# design.net
KiCad netlist of a schematic drawn in Altium Designer
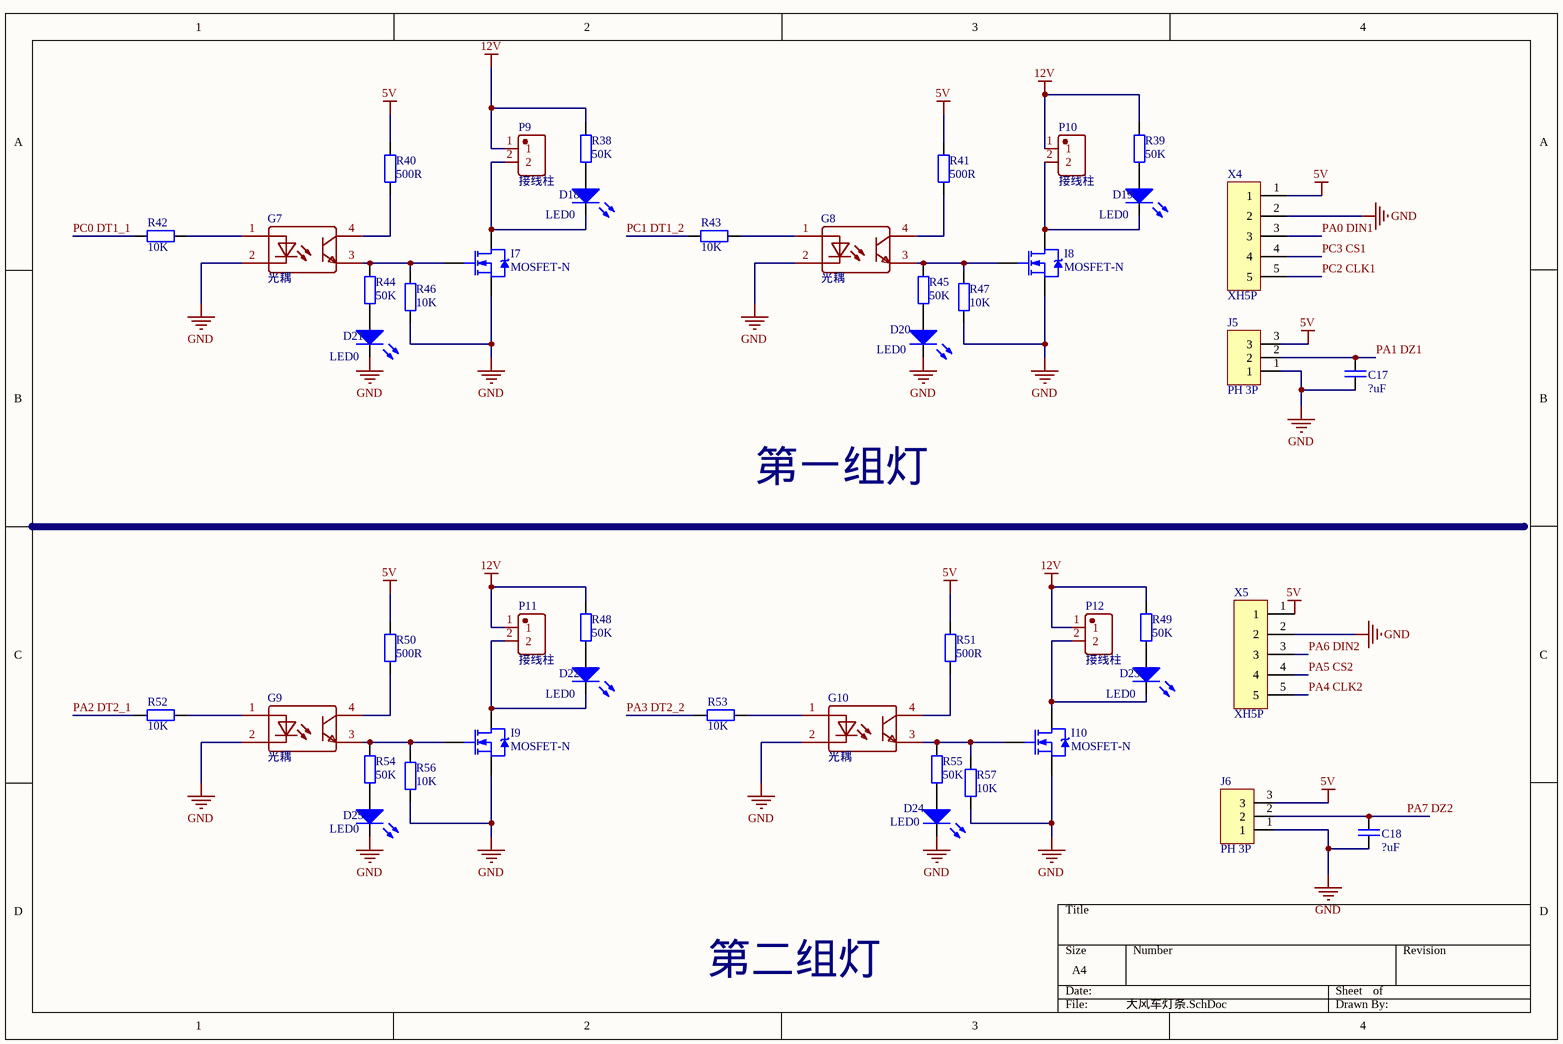
[diagram p0: 大风车灯条.SchDoc]

(export (version "E")
  (design (tool "Eeschema 10.0.6"))
  (components
    (comp (ref "C17")
      (value "?uF")
      (footprint "0603_C")
      (fields (field (name "PUBLISHER") "Altium Limited"))
      (libsource (lib "电容-电阻-电感") (part "Cap"))
    )
    (comp (ref "C18")
      (value "?uF")
      (footprint "0603_C")
      (fields (field (name "PUBLISHER") "Altium Limited"))
      (libsource (lib "电容-电阻-电感") (part "Cap"))
    )
    (comp (ref "D18")
      (value "LED0")
      (footprint "LED-0603")
      (description "发光二极管")
      (fields (field (name "PUBLISHER") "Altium Limited"))
      (libsource (lib "二极管-晶体管") (part "LED0"))
    )
    (comp (ref "D19")
      (value "LED0")
      (footprint "LED-0603")
      (description "发光二极管")
      (fields (field (name "PUBLISHER") "Altium Limited"))
      (libsource (lib "二极管-晶体管") (part "LED0"))
    )
    (comp (ref "D20")
      (value "LED0")
      (footprint "LED-0603")
      (description "发光二极管")
      (fields (field (name "PUBLISHER") "Altium Limited"))
      (libsource (lib "二极管-晶体管") (part "LED0"))
    )
    (comp (ref "D21")
      (value "LED0")
      (footprint "LED-0603")
      (description "发光二极管")
      (fields (field (name "PUBLISHER") "Altium Limited"))
      (libsource (lib "二极管-晶体管") (part "LED0"))
    )
    (comp (ref "D22")
      (value "LED0")
      (footprint "LED-0603")
      (description "发光二极管")
      (fields (field (name "PUBLISHER") "Altium Limited"))
      (libsource (lib "二极管-晶体管") (part "LED0"))
    )
    (comp (ref "D23")
      (value "LED0")
      (footprint "LED-0603")
      (description "发光二极管")
      (fields (field (name "PUBLISHER") "Altium Limited"))
      (libsource (lib "二极管-晶体管") (part "LED0"))
    )
    (comp (ref "D24")
      (value "LED0")
      (footprint "LED-0603")
      (description "发光二极管")
      (fields (field (name "PUBLISHER") "Altium Limited"))
      (libsource (lib "二极管-晶体管") (part "LED0"))
    )
    (comp (ref "D25")
      (value "LED0")
      (footprint "LED-0603")
      (description "发光二极管")
      (fields (field (name "PUBLISHER") "Altium Limited"))
      (libsource (lib "二极管-晶体管") (part "LED0"))
    )
    (comp (ref "G7") (value "光耦") (footprint "SMD-4") (libsource (lib "大风车") (part "光耦")))
    (comp (ref "G8") (value "光耦") (footprint "SMD-4") (libsource (lib "大风车") (part "光耦")))
    (comp (ref "G9") (value "光耦") (footprint "SMD-4") (libsource (lib "大风车") (part "光耦")))
    (comp (ref "G10") (value "光耦") (footprint "SMD-4") (libsource (lib "大风车") (part "光耦")))
    (comp (ref "I7") (value "MOSFET-N") (footprint "VSONP-8") (libsource (lib "大风兄弟") (part "MOSFET-N")))
    (comp (ref "I8") (value "MOSFET-N") (footprint "VSONP-8") (libsource (lib "大风兄弟") (part "MOSFET-N")))
    (comp (ref "I9") (value "MOSFET-N") (footprint "VSONP-8") (libsource (lib "大风兄弟") (part "MOSFET-N")))
    (comp (ref "I10") (value "MOSFET-N") (footprint "VSONP-8") (libsource (lib "大风兄弟") (part "MOSFET-N")))
    (comp (ref "J5") (value "PH 3P") (footprint "PH3P") (libsource (lib "连接器") (part "PH 3P")))
    (comp (ref "J6") (value "PH 3P") (footprint "PH3P") (libsource (lib "连接器") (part "PH 3P")))
    (comp (ref "P9") (value "接线柱") (footprint "XT30-F") (libsource (lib "大风车") (part "接线柱")))
    (comp (ref "P10") (value "接线柱") (footprint "XT30-F") (libsource (lib "大风车") (part "接线柱")))
    (comp (ref "P11") (value "接线柱") (footprint "XT30-F") (libsource (lib "大风车") (part "接线柱")))
    (comp (ref "P12") (value "接线柱") (footprint "XT30-F") (libsource (lib "大风车") (part "接线柱")))
    (comp (ref "R38")
      (value "50K")
      (footprint "0603_R")
      (fields (field (name "PUBLISHER") "Altium Limited"))
      (libsource (lib "") (part "Res_1"))
    )
    (comp (ref "R39")
      (value "50K")
      (footprint "0603_R")
      (fields (field (name "PUBLISHER") "Altium Limited"))
      (libsource (lib "") (part "Res_1"))
    )
    (comp (ref "R40")
      (value "500R")
      (footprint "0603_R")
      (fields (field (name "PUBLISHER") "Altium Limited"))
      (libsource (lib "") (part "Res_1"))
    )
    (comp (ref "R41")
      (value "500R")
      (footprint "0603_R")
      (fields (field (name "PUBLISHER") "Altium Limited"))
      (libsource (lib "") (part "Res_1"))
    )
    (comp (ref "R42")
      (value "10K")
      (footprint "0603_R")
      (fields (field (name "PUBLISHER") "Altium Limited"))
      (libsource (lib "电容-电阻-电感") (part "Res"))
    )
    (comp (ref "R43")
      (value "10K")
      (footprint "0603_R")
      (fields (field (name "PUBLISHER") "Altium Limited"))
      (libsource (lib "电容-电阻-电感") (part "Res"))
    )
    (comp (ref "R44")
      (value "50K")
      (footprint "0603_R")
      (fields (field (name "PUBLISHER") "Altium Limited"))
      (libsource (lib "") (part "Res_1"))
    )
    (comp (ref "R45")
      (value "50K")
      (footprint "0603_R")
      (fields (field (name "PUBLISHER") "Altium Limited"))
      (libsource (lib "") (part "Res_1"))
    )
    (comp (ref "R46")
      (value "10K")
      (footprint "0603_R")
      (fields (field (name "PUBLISHER") "Altium Limited"))
      (libsource (lib "") (part "Res_1"))
    )
    (comp (ref "R47")
      (value "10K")
      (footprint "0603_R")
      (fields (field (name "PUBLISHER") "Altium Limited"))
      (libsource (lib "") (part "Res_1"))
    )
    (comp (ref "R48")
      (value "50K")
      (footprint "0603_R")
      (fields (field (name "PUBLISHER") "Altium Limited"))
      (libsource (lib "") (part "Res_1"))
    )
    (comp (ref "R49")
      (value "50K")
      (footprint "0603_R")
      (fields (field (name "PUBLISHER") "Altium Limited"))
      (libsource (lib "") (part "Res_1"))
    )
    (comp (ref "R50")
      (value "500R")
      (footprint "0603_R")
      (fields (field (name "PUBLISHER") "Altium Limited"))
      (libsource (lib "") (part "Res_1"))
    )
    (comp (ref "R51")
      (value "500R")
      (footprint "0603_R")
      (fields (field (name "PUBLISHER") "Altium Limited"))
      (libsource (lib "") (part "Res_1"))
    )
    (comp (ref "R52")
      (value "10K")
      (footprint "0603_R")
      (fields (field (name "PUBLISHER") "Altium Limited"))
      (libsource (lib "电容-电阻-电感") (part "Res"))
    )
    (comp (ref "R53")
      (value "10K")
      (footprint "0603_R")
      (fields (field (name "PUBLISHER") "Altium Limited"))
      (libsource (lib "电容-电阻-电感") (part "Res"))
    )
    (comp (ref "R54")
      (value "50K")
      (footprint "0603_R")
      (fields (field (name "PUBLISHER") "Altium Limited"))
      (libsource (lib "") (part "Res_1"))
    )
    (comp (ref "R55")
      (value "50K")
      (footprint "0603_R")
      (fields (field (name "PUBLISHER") "Altium Limited"))
      (libsource (lib "") (part "Res_1"))
    )
    (comp (ref "R56")
      (value "10K")
      (footprint "0603_R")
      (fields (field (name "PUBLISHER") "Altium Limited"))
      (libsource (lib "") (part "Res_1"))
    )
    (comp (ref "R57")
      (value "10K")
      (footprint "0603_R")
      (fields (field (name "PUBLISHER") "Altium Limited"))
      (libsource (lib "") (part "Res_1"))
    )
    (comp (ref "X4") (value "XH5P") (footprint "XH5P") (libsource (lib "大风车") (part "XH5P")))
    (comp (ref "X5") (value "XH5P") (footprint "XH5P") (libsource (lib "大风车") (part "XH5P")))
  )
  (nets
    (net (code "1") (name "/PA0 DIN1") (class "Default")
      (node (ref "X4") (pin "3") (pinfunction "3_3") (pintype "passive"))
    )
    (net (code "2") (name "/PA1 DZ1") (class "Default")
      (node (ref "C17") (pin "2") (pinfunction "2_2") (pintype "passive"))
      (node (ref "J5") (pin "2") (pinfunction "2_2") (pintype "power_in"))
    )
    (net (code "3") (name "/PA2 DT2_1") (class "Default")
      (node (ref "R52") (pin "1") (pinfunction "1_1") (pintype "passive"))
    )
    (net (code "4") (name "/PA3 DT2_2") (class "Default")
      (node (ref "R53") (pin "1") (pinfunction "1_1") (pintype "passive"))
    )
    (net (code "5") (name "/PA4 CLK2") (class "Default")
      (node (ref "X5") (pin "5") (pinfunction "5_5") (pintype "power_in"))
    )
    (net (code "6") (name "/PA5 CS2") (class "Default")
      (node (ref "X5") (pin "4") (pinfunction "4_4") (pintype "passive"))
    )
    (net (code "7") (name "/PA6 DIN2") (class "Default")
      (node (ref "X5") (pin "3") (pinfunction "3_3") (pintype "passive"))
    )
    (net (code "8") (name "/PA7 DZ2") (class "Default")
      (node (ref "C18") (pin "2") (pinfunction "2_2") (pintype "passive"))
      (node (ref "J6") (pin "2") (pinfunction "2_2") (pintype "power_in"))
    )
    (net (code "9") (name "/PC0 DT1_1") (class "Default")
      (node (ref "R42") (pin "1") (pinfunction "1_1") (pintype "passive"))
    )
    (net (code "10") (name "/PC1 DT1_2") (class "Default")
      (node (ref "R43") (pin "1") (pinfunction "1_1") (pintype "passive"))
    )
    (net (code "11") (name "/PC2 CLK1") (class "Default")
      (node (ref "X4") (pin "5") (pinfunction "5_5") (pintype "power_in"))
    )
    (net (code "12") (name "/PC3 CS1") (class "Default")
      (node (ref "X4") (pin "4") (pinfunction "4_4") (pintype "passive"))
    )
    (net (code "13") (name "5V") (class "Default")
      (node (ref "J5") (pin "3") (pinfunction "3_3") (pintype "power_in"))
      (node (ref "J6") (pin "3") (pinfunction "3_3") (pintype "power_in"))
      (node (ref "R40") (pin "2") (pinfunction "2_2") (pintype "passive"))
      (node (ref "R41") (pin "2") (pinfunction "2_2") (pintype "passive"))
      (node (ref "R50") (pin "2") (pinfunction "2_2") (pintype "passive"))
      (node (ref "R51") (pin "2") (pinfunction "2_2") (pintype "passive"))
      (node (ref "X4") (pin "1") (pinfunction "1_1") (pintype "passive"))
      (node (ref "X5") (pin "1") (pinfunction "1_1") (pintype "passive"))
    )
    (net (code "14") (name "12V") (class "Default")
      (node (ref "P10") (pin "1") (pinfunction "1_1") (pintype "passive"))
      (node (ref "P11") (pin "1") (pinfunction "1_1") (pintype "passive"))
      (node (ref "P12") (pin "1") (pinfunction "1_1") (pintype "passive"))
      (node (ref "P9") (pin "1") (pinfunction "1_1") (pintype "passive"))
      (node (ref "R38") (pin "2") (pinfunction "2_2") (pintype "passive"))
      (node (ref "R39") (pin "2") (pinfunction "2_2") (pintype "passive"))
      (node (ref "R48") (pin "2") (pinfunction "2_2") (pintype "passive"))
      (node (ref "R49") (pin "2") (pinfunction "2_2") (pintype "passive"))
    )
    (net (code "15") (name "GND") (class "Default")
      (node (ref "C17") (pin "1") (pinfunction "1_1") (pintype "passive"))
      (node (ref "C18") (pin "1") (pinfunction "1_1") (pintype "passive"))
      (node (ref "D20") (pin "2") (pinfunction "K_2") (pintype "passive"))
      (node (ref "D21") (pin "2") (pinfunction "K_2") (pintype "passive"))
      (node (ref "D24") (pin "2") (pinfunction "K_2") (pintype "passive"))
      (node (ref "D25") (pin "2") (pinfunction "K_2") (pintype "passive"))
      (node (ref "G10") (pin "2") (pinfunction "CAT_2") (pintype "passive"))
      (node (ref "G7") (pin "2") (pinfunction "CAT_2") (pintype "passive"))
      (node (ref "G8") (pin "2") (pinfunction "CAT_2") (pintype "passive"))
      (node (ref "G9") (pin "2") (pinfunction "CAT_2") (pintype "passive"))
      (node (ref "I10") (pin "S") (pinfunction "S_S") (pintype "passive"))
      (node (ref "I7") (pin "S") (pinfunction "S_S") (pintype "passive"))
      (node (ref "I8") (pin "S") (pinfunction "S_S") (pintype "passive"))
      (node (ref "I9") (pin "S") (pinfunction "S_S") (pintype "passive"))
      (node (ref "J5") (pin "1") (pinfunction "1_1") (pintype "power_in"))
      (node (ref "J6") (pin "1") (pinfunction "1_1") (pintype "power_in"))
      (node (ref "R46") (pin "1") (pinfunction "1_1") (pintype "passive"))
      (node (ref "R47") (pin "1") (pinfunction "1_1") (pintype "passive"))
      (node (ref "R56") (pin "1") (pinfunction "1_1") (pintype "passive"))
      (node (ref "R57") (pin "1") (pinfunction "1_1") (pintype "passive"))
      (node (ref "X4") (pin "2") (pinfunction "2_2") (pintype "passive"))
      (node (ref "X5") (pin "2") (pinfunction "2_2") (pintype "passive"))
    )
    (net (code "16") (name "Net-(D18-A)") (class "Default")
      (node (ref "D18") (pin "1") (pinfunction "A_1") (pintype "passive"))
      (node (ref "R38") (pin "1") (pinfunction "1_1") (pintype "passive"))
    )
    (net (code "17") (name "Net-(D18-K)") (class "Default")
      (node (ref "D18") (pin "2") (pinfunction "K_2") (pintype "passive"))
      (node (ref "I7") (pin "D") (pinfunction "D_D") (pintype "passive"))
      (node (ref "P9") (pin "2") (pinfunction "2_2") (pintype "passive"))
    )
    (net (code "18") (name "Net-(D19-A)") (class "Default")
      (node (ref "D19") (pin "1") (pinfunction "A_1") (pintype "passive"))
      (node (ref "R39") (pin "1") (pinfunction "1_1") (pintype "passive"))
    )
    (net (code "19") (name "Net-(D19-K)") (class "Default")
      (node (ref "D19") (pin "2") (pinfunction "K_2") (pintype "passive"))
      (node (ref "I8") (pin "D") (pinfunction "D_D") (pintype "passive"))
      (node (ref "P10") (pin "2") (pinfunction "2_2") (pintype "passive"))
    )
    (net (code "20") (name "Net-(D20-A)") (class "Default")
      (node (ref "D20") (pin "1") (pinfunction "A_1") (pintype "passive"))
      (node (ref "R45") (pin "1") (pinfunction "1_1") (pintype "passive"))
    )
    (net (code "21") (name "Net-(D21-A)") (class "Default")
      (node (ref "D21") (pin "1") (pinfunction "A_1") (pintype "passive"))
      (node (ref "R44") (pin "1") (pinfunction "1_1") (pintype "passive"))
    )
    (net (code "22") (name "Net-(D22-A)") (class "Default")
      (node (ref "D22") (pin "1") (pinfunction "A_1") (pintype "passive"))
      (node (ref "R48") (pin "1") (pinfunction "1_1") (pintype "passive"))
    )
    (net (code "23") (name "Net-(D22-K)") (class "Default")
      (node (ref "D22") (pin "2") (pinfunction "K_2") (pintype "passive"))
      (node (ref "I9") (pin "D") (pinfunction "D_D") (pintype "passive"))
      (node (ref "P11") (pin "2") (pinfunction "2_2") (pintype "passive"))
    )
    (net (code "24") (name "Net-(D23-A)") (class "Default")
      (node (ref "D23") (pin "1") (pinfunction "A_1") (pintype "passive"))
      (node (ref "R49") (pin "1") (pinfunction "1_1") (pintype "passive"))
    )
    (net (code "25") (name "Net-(D23-K)") (class "Default")
      (node (ref "D23") (pin "2") (pinfunction "K_2") (pintype "passive"))
      (node (ref "I10") (pin "D") (pinfunction "D_D") (pintype "passive"))
      (node (ref "P12") (pin "2") (pinfunction "2_2") (pintype "passive"))
    )
    (net (code "26") (name "Net-(D24-A)") (class "Default")
      (node (ref "D24") (pin "1") (pinfunction "A_1") (pintype "passive"))
      (node (ref "R55") (pin "1") (pinfunction "1_1") (pintype "passive"))
    )
    (net (code "27") (name "Net-(D25-A)") (class "Default")
      (node (ref "D25") (pin "1") (pinfunction "A_1") (pintype "passive"))
      (node (ref "R54") (pin "1") (pinfunction "1_1") (pintype "passive"))
    )
    (net (code "28") (name "Net-(G7-AN)") (class "Default")
      (node (ref "G7") (pin "1") (pinfunction "AN_1") (pintype "passive"))
      (node (ref "R42") (pin "2") (pinfunction "2_2") (pintype "passive"))
    )
    (net (code "29") (name "Net-(G7-COL)") (class "Default")
      (node (ref "G7") (pin "4") (pinfunction "COL_4") (pintype "passive"))
      (node (ref "R40") (pin "1") (pinfunction "1_1") (pintype "passive"))
    )
    (net (code "30") (name "Net-(G7-EM)") (class "Default")
      (node (ref "G7") (pin "3") (pinfunction "EM_3") (pintype "passive"))
      (node (ref "I7") (pin "G") (pinfunction "G_G") (pintype "passive"))
      (node (ref "R44") (pin "2") (pinfunction "2_2") (pintype "passive"))
      (node (ref "R46") (pin "2") (pinfunction "2_2") (pintype "passive"))
    )
    (net (code "31") (name "Net-(G8-AN)") (class "Default")
      (node (ref "G8") (pin "1") (pinfunction "AN_1") (pintype "passive"))
      (node (ref "R43") (pin "2") (pinfunction "2_2") (pintype "passive"))
    )
    (net (code "32") (name "Net-(G8-COL)") (class "Default")
      (node (ref "G8") (pin "4") (pinfunction "COL_4") (pintype "passive"))
      (node (ref "R41") (pin "1") (pinfunction "1_1") (pintype "passive"))
    )
    (net (code "33") (name "Net-(G8-EM)") (class "Default")
      (node (ref "G8") (pin "3") (pinfunction "EM_3") (pintype "passive"))
      (node (ref "I8") (pin "G") (pinfunction "G_G") (pintype "passive"))
      (node (ref "R45") (pin "2") (pinfunction "2_2") (pintype "passive"))
      (node (ref "R47") (pin "2") (pinfunction "2_2") (pintype "passive"))
    )
    (net (code "34") (name "Net-(G9-AN)") (class "Default")
      (node (ref "G9") (pin "1") (pinfunction "AN_1") (pintype "passive"))
      (node (ref "R52") (pin "2") (pinfunction "2_2") (pintype "passive"))
    )
    (net (code "35") (name "Net-(G9-COL)") (class "Default")
      (node (ref "G9") (pin "4") (pinfunction "COL_4") (pintype "passive"))
      (node (ref "R50") (pin "1") (pinfunction "1_1") (pintype "passive"))
    )
    (net (code "36") (name "Net-(G9-EM)") (class "Default")
      (node (ref "G9") (pin "3") (pinfunction "EM_3") (pintype "passive"))
      (node (ref "I9") (pin "G") (pinfunction "G_G") (pintype "passive"))
      (node (ref "R54") (pin "2") (pinfunction "2_2") (pintype "passive"))
      (node (ref "R56") (pin "2") (pinfunction "2_2") (pintype "passive"))
    )
    (net (code "37") (name "Net-(G10-AN)") (class "Default")
      (node (ref "G10") (pin "1") (pinfunction "AN_1") (pintype "passive"))
      (node (ref "R53") (pin "2") (pinfunction "2_2") (pintype "passive"))
    )
    (net (code "38") (name "Net-(G10-COL)") (class "Default")
      (node (ref "G10") (pin "4") (pinfunction "COL_4") (pintype "passive"))
      (node (ref "R51") (pin "1") (pinfunction "1_1") (pintype "passive"))
    )
    (net (code "39") (name "Net-(G10-EM)") (class "Default")
      (node (ref "G10") (pin "3") (pinfunction "EM_3") (pintype "passive"))
      (node (ref "I10") (pin "G") (pinfunction "G_G") (pintype "passive"))
      (node (ref "R55") (pin "2") (pinfunction "2_2") (pintype "passive"))
      (node (ref "R57") (pin "2") (pinfunction "2_2") (pintype "passive"))
    )
  )
)
